# Sheet2.net
KiCad netlist of a schematic drawn in Altium Designer
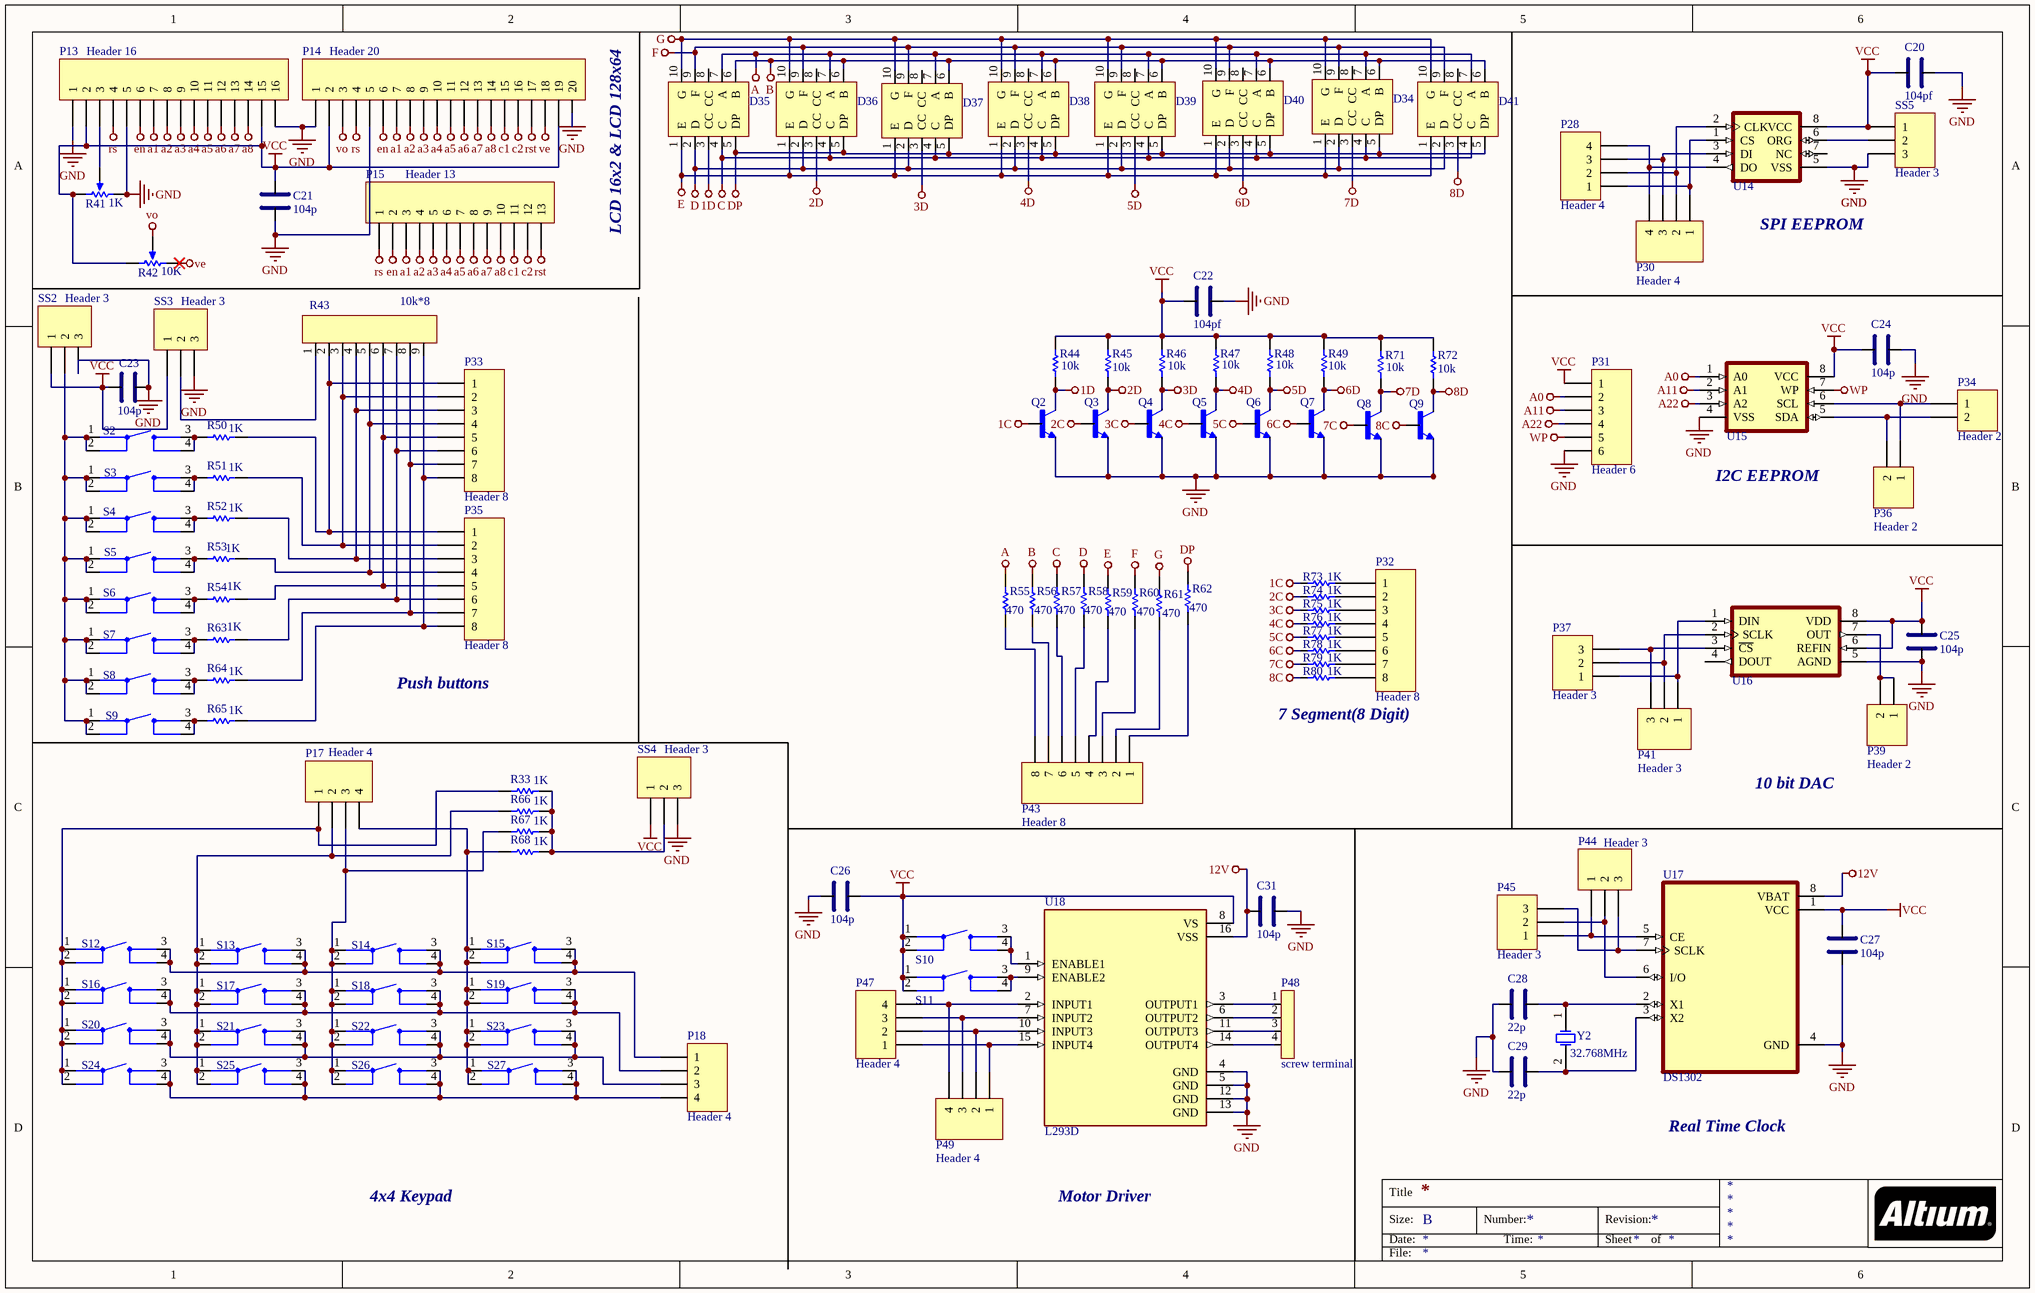
[diagram p0: Sheet2.SchDoc]

(export (version "E")
  (design (tool "Eeschema 10.0.6"))
  (components
    (comp (ref "C20")
      (value "104pf")
      (footprint "cap")
      (fields (field (name "Comment") "cap"))
      (libsource (lib "CAP") (part "cap"))
    )
    (comp (ref "C21")
      (value "104p")
      (footprint "cap")
      (fields (field (name "Comment") "cap"))
      (libsource (lib "CAP") (part "cap"))
    )
    (comp (ref "C22")
      (value "104pf")
      (footprint "cap")
      (fields (field (name "Comment") "cap"))
      (libsource (lib "CAP") (part "cap"))
    )
    (comp (ref "C23")
      (value "104p")
      (footprint "cap")
      (fields (field (name "Comment") "cap"))
      (libsource (lib "CAP") (part "cap"))
    )
    (comp (ref "C24")
      (value "104p")
      (footprint "cap")
      (fields (field (name "Comment") "cap"))
      (libsource (lib "CAP") (part "cap"))
    )
    (comp (ref "C25")
      (value "104p")
      (footprint "cap")
      (fields (field (name "Comment") "cap"))
      (libsource (lib "CAP") (part "cap"))
    )
    (comp (ref "C26")
      (value "104p")
      (footprint "cap")
      (fields (field (name "Comment") "cap"))
      (libsource (lib "CAP") (part "cap"))
    )
    (comp (ref "C27")
      (value "104p")
      (footprint "cap")
      (fields (field (name "Comment") "cap"))
      (libsource (lib "CAP") (part "cap"))
    )
    (comp (ref "C28")
      (value "22p")
      (footprint "cap")
      (fields (field (name "Comment") "cap"))
      (libsource (lib "CAP") (part "cap"))
    )
    (comp (ref "C29")
      (value "22p")
      (footprint "cap")
      (fields (field (name "Comment") "cap"))
      (libsource (lib "CAP") (part "cap"))
    )
    (comp (ref "C31")
      (value "104p")
      (footprint "cap")
      (fields (field (name "Comment") "cap"))
      (libsource (lib "CAP") (part "cap"))
    )
    (comp (ref "D34") (value "7seg") (footprint "LED_LTD-4708G") (libsource (lib "7seg") (part "7seg")))
    (comp (ref "D35") (value "7seg") (footprint "LED_LTD-4708G") (libsource (lib "7seg") (part "7seg")))
    (comp (ref "D36") (value "7seg") (footprint "LED_LTD-4708G") (libsource (lib "7seg") (part "7seg")))
    (comp (ref "D37") (value "7seg") (footprint "LED_LTD-4708G") (libsource (lib "7seg") (part "7seg")))
    (comp (ref "D38") (value "7seg") (footprint "LED_LTD-4708G") (libsource (lib "7seg") (part "7seg")))
    (comp (ref "D39") (value "7seg") (footprint "LED_LTD-4708G") (libsource (lib "7seg") (part "7seg")))
    (comp (ref "D40") (value "7seg") (footprint "LED_LTD-4708G") (libsource (lib "7seg") (part "7seg")))
    (comp (ref "D41") (value "7seg") (footprint "LED_LTD-4708G") (libsource (lib "7seg") (part "7seg")))
    (comp (ref "P13")
      (value "Header 16")
      (footprint "HDR1X16")
      (description "Header, 16-Pin")
      (fields (field (name "PUBLISHER") "Altium Limited"))
      (libsource (lib "Miscellaneous Connectors") (part "Header 16"))
    )
    (comp (ref "P14")
      (value "Header 20")
      (footprint "HDR1X20")
      (description "Header, 20-Pin")
      (fields (field (name "PUBLISHER") "Altium Limited"))
      (libsource (lib "Miscellaneous Connectors") (part "Header 20"))
    )
    (comp (ref "P15")
      (value "Header 13")
      (footprint "HDR1X13")
      (description "Header, 13-Pin")
      (fields (field (name "PUBLISHER") "Altium Limited"))
      (libsource (lib "Miscellaneous Connectors") (part "Header 13"))
    )
    (comp (ref "P17")
      (value "Header 4")
      (footprint "HDR1X4")
      (description "Header, 4-Pin")
      (fields (field (name "PUBLISHER") "Altium Limited"))
      (libsource (lib "") (part "Header 4_2"))
    )
    (comp (ref "P18")
      (value "Header 4")
      (footprint "HDR1X4")
      (description "Header, 4-Pin")
      (fields (field (name "PUBLISHER") "Altium Limited"))
      (libsource (lib "") (part "Header 4_3"))
    )
    (comp (ref "P28")
      (value "Header 4")
      (footprint "HDR1X4")
      (description "Header, 4-Pin")
      (fields (field (name "PUBLISHER") "Altium Limited"))
      (libsource (lib "Miscellaneous Connectors") (part "Header 4"))
    )
    (comp (ref "P30")
      (value "Header 4")
      (footprint "HDR1X4")
      (description "Header, 4-Pin")
      (fields (field (name "PUBLISHER") "Altium Limited"))
      (libsource (lib "") (part "Header 4_1"))
    )
    (comp (ref "P31")
      (value "Header 6")
      (footprint "HDR1X6")
      (description "Header, 6-Pin")
      (fields (field (name "PUBLISHER") "Altium Limited"))
      (libsource (lib "Miscellaneous Connectors") (part "Header 6"))
    )
    (comp (ref "P32")
      (value "Header 8")
      (footprint "HDR1X8")
      (description "Header, 8-Pin")
      (fields (field (name "PUBLISHER") "Altium Limited"))
      (libsource (lib "") (part "Header 8_1"))
    )
    (comp (ref "P33")
      (value "Header 8")
      (footprint "HDR1X8")
      (description "Header, 8-Pin")
      (fields (field (name "PUBLISHER") "Altium Limited"))
      (libsource (lib "") (part "Header 8_1"))
    )
    (comp (ref "P34")
      (value "Header 2")
      (footprint "HDR1X2")
      (description "Header, 2-Pin")
      (fields (field (name "PUBLISHER") "Altium Limited"))
      (libsource (lib "Miscellaneous Connectors") (part "Header 2"))
    )
    (comp (ref "P35")
      (value "Header 8")
      (footprint "HDR1X8")
      (description "Header, 8-Pin")
      (fields (field (name "PUBLISHER") "Altium Limited"))
      (libsource (lib "") (part "Header 8_1"))
    )
    (comp (ref "P36")
      (value "Header 2")
      (footprint "HDR1X2")
      (description "Header, 2-Pin")
      (fields (field (name "PUBLISHER") "Altium Limited"))
      (libsource (lib "") (part "Header 2_1"))
    )
    (comp (ref "P37")
      (value "Header 3")
      (footprint "HDR1X3")
      (description "Header, 3-Pin")
      (fields (field (name "PUBLISHER") "Altium Limited"))
      (libsource (lib "") (part "Header 3_3"))
    )
    (comp (ref "P39")
      (value "Header 2")
      (footprint "HDR1X2")
      (description "Header, 2-Pin")
      (fields (field (name "PUBLISHER") "Altium Limited"))
      (libsource (lib "") (part "Header 2_1"))
    )
    (comp (ref "P41")
      (value "Header 3")
      (footprint "HDR1X3")
      (description "Header, 3-Pin")
      (fields (field (name "PUBLISHER") "Altium Limited"))
      (libsource (lib "") (part "Header 3_1"))
    )
    (comp (ref "P43")
      (value "Header 8")
      (footprint "HDR1X8")
      (description "Header, 8-Pin")
      (fields (field (name "PUBLISHER") "Altium Limited"))
      (libsource (lib "Miscellaneous Connectors") (part "Header 8"))
    )
    (comp (ref "P44")
      (value "Header 3")
      (footprint "HDR1X3")
      (description "Header, 3-Pin")
      (fields (field (name "PUBLISHER") "Altium Limited"))
      (libsource (lib "Miscellaneous Connectors") (part "Header 3"))
    )
    (comp (ref "P45")
      (value "Header 3")
      (footprint "HDR1X3")
      (description "Header, 3-Pin")
      (fields (field (name "PUBLISHER") "Altium Limited"))
      (libsource (lib "") (part "Header 3_3"))
    )
    (comp (ref "P47")
      (value "Header 4")
      (footprint "HDR1X4")
      (description "Header, 4-Pin")
      (fields (field (name "PUBLISHER") "Altium Limited"))
      (libsource (lib "Miscellaneous Connectors") (part "Header 4"))
    )
    (comp (ref "P48")
      (value "screw terminal")
      (footprint "screw library")
      (libsource (lib "screw terminal") (part "screw terminal"))
    )
    (comp (ref "P49")
      (value "Header 4")
      (footprint "HDR1X4")
      (description "Header, 4-Pin")
      (fields (field (name "PUBLISHER") "Altium Limited"))
      (libsource (lib "") (part "Header 4_1"))
    )
    (comp (ref "Q2")
      (value "2N5172")
      (footprint "TRANSISTOR_TO-92:TRANSISTOR_TO-92")
      (description "Bipolar (BJT) Transistor NPN 25V 500mA 625mW Through Hole TO-92-3")
      (fields (field (name "MF") "ON Semiconductor"))
      (libsource (lib "2N5172") (part "2N5172"))
    )
    (comp (ref "Q3")
      (value "2N5172")
      (footprint "TRANSISTOR_TO-92:TRANSISTOR_TO-92")
      (description "Bipolar (BJT) Transistor NPN 25V 500mA 625mW Through Hole TO-92-3")
      (fields (field (name "MF") "ON Semiconductor"))
      (libsource (lib "2N5172") (part "2N5172"))
    )
    (comp (ref "Q4")
      (value "2N5172")
      (footprint "TRANSISTOR_TO-92:TRANSISTOR_TO-92")
      (description "Bipolar (BJT) Transistor NPN 25V 500mA 625mW Through Hole TO-92-3")
      (fields (field (name "MF") "ON Semiconductor"))
      (libsource (lib "2N5172") (part "2N5172"))
    )
    (comp (ref "Q5")
      (value "2N5172")
      (footprint "TRANSISTOR_TO-92:TRANSISTOR_TO-92")
      (description "Bipolar (BJT) Transistor NPN 25V 500mA 625mW Through Hole TO-92-3")
      (fields (field (name "MF") "ON Semiconductor"))
      (libsource (lib "2N5172") (part "2N5172"))
    )
    (comp (ref "Q6")
      (value "2N5172")
      (footprint "TRANSISTOR_TO-92:TRANSISTOR_TO-92")
      (description "Bipolar (BJT) Transistor NPN 25V 500mA 625mW Through Hole TO-92-3")
      (fields (field (name "MF") "ON Semiconductor"))
      (libsource (lib "2N5172") (part "2N5172"))
    )
    (comp (ref "Q7")
      (value "2N5172")
      (footprint "TRANSISTOR_TO-92:TRANSISTOR_TO-92")
      (description "Bipolar (BJT) Transistor NPN 25V 500mA 625mW Through Hole TO-92-3")
      (fields (field (name "MF") "ON Semiconductor"))
      (libsource (lib "2N5172") (part "2N5172"))
    )
    (comp (ref "Q8")
      (value "2N5172")
      (footprint "TRANSISTOR_TO-92:TRANSISTOR_TO-92")
      (description "Bipolar (BJT) Transistor NPN 25V 500mA 625mW Through Hole TO-92-3")
      (fields (field (name "MF") "ON Semiconductor"))
      (libsource (lib "2N5172") (part "2N5172"))
    )
    (comp (ref "Q9")
      (value "2N5172")
      (footprint "TRANSISTOR_TO-92:TRANSISTOR_TO-92")
      (description "Bipolar (BJT) Transistor NPN 25V 500mA 625mW Through Hole TO-92-3")
      (fields (field (name "MF") "ON Semiconductor"))
      (libsource (lib "2N5172") (part "2N5172"))
    )
    (comp (ref "R33")
      (value "1K")
      (footprint "AXIAL-0.3")
      (description "Resistor")
      (fields (field (name "Comment") "Res1") (field (name "PUBLISHER") "Altium Limited"))
      (libsource (lib "Miscellaneous Devices") (part "Res1"))
    )
    (comp (ref "R41")
      (value "1K")
      (footprint "VR5")
      (description "Potentiometer")
      (fields (field (name "Comment") "RPot") (field (name "PUBLISHER") "Altium Limited"))
      (libsource (lib "Miscellaneous Devices") (part "RPot"))
    )
    (comp (ref "R42")
      (value "10K")
      (footprint "VR5")
      (description "Potentiometer")
      (fields (field (name "Comment") "RPot") (field (name "PUBLISHER") "Altium Limited"))
      (libsource (lib "Miscellaneous Devices") (part "RPot"))
    )
    (comp (ref "R43")
      (value "10k*8")
      (footprint "10k sip")
      (fields (field (name "Comment") "10k sip"))
      (libsource (lib "10k sip") (part "10k sip"))
    )
    (comp (ref "R44")
      (value "10k")
      (footprint "AXIAL-0.3")
      (description "Resistor")
      (fields (field (name "Comment") "Res1") (field (name "PUBLISHER") "Altium Limited"))
      (libsource (lib "Miscellaneous Devices") (part "Res1"))
    )
    (comp (ref "R45")
      (value "10k")
      (footprint "AXIAL-0.3")
      (description "Resistor")
      (fields (field (name "Comment") "Res1") (field (name "PUBLISHER") "Altium Limited"))
      (libsource (lib "Miscellaneous Devices") (part "Res1"))
    )
    (comp (ref "R46")
      (value "10k")
      (footprint "AXIAL-0.3")
      (description "Resistor")
      (fields (field (name "Comment") "Res1") (field (name "PUBLISHER") "Altium Limited"))
      (libsource (lib "Miscellaneous Devices") (part "Res1"))
    )
    (comp (ref "R47")
      (value "10k")
      (footprint "AXIAL-0.3")
      (description "Resistor")
      (fields (field (name "Comment") "Res1") (field (name "PUBLISHER") "Altium Limited"))
      (libsource (lib "Miscellaneous Devices") (part "Res1"))
    )
    (comp (ref "R48")
      (value "10k")
      (footprint "AXIAL-0.3")
      (description "Resistor")
      (fields (field (name "Comment") "Res1") (field (name "PUBLISHER") "Altium Limited"))
      (libsource (lib "Miscellaneous Devices") (part "Res1"))
    )
    (comp (ref "R49")
      (value "10k")
      (footprint "AXIAL-0.3")
      (description "Resistor")
      (fields (field (name "Comment") "Res1") (field (name "PUBLISHER") "Altium Limited"))
      (libsource (lib "Miscellaneous Devices") (part "Res1"))
    )
    (comp (ref "R50")
      (value "1K")
      (footprint "AXIAL-0.3")
      (description "Resistor")
      (fields (field (name "Comment") "Res1") (field (name "PUBLISHER") "Altium Limited"))
      (libsource (lib "Miscellaneous Devices") (part "Res1"))
    )
    (comp (ref "R51")
      (value "1K")
      (footprint "AXIAL-0.3")
      (description "Resistor")
      (fields (field (name "Comment") "Res1") (field (name "PUBLISHER") "Altium Limited"))
      (libsource (lib "Miscellaneous Devices") (part "Res1"))
    )
    (comp (ref "R52")
      (value "1K")
      (footprint "AXIAL-0.3")
      (description "Resistor")
      (fields (field (name "Comment") "Res1") (field (name "PUBLISHER") "Altium Limited"))
      (libsource (lib "Miscellaneous Devices") (part "Res1"))
    )
    (comp (ref "R53")
      (value "1K")
      (footprint "AXIAL-0.3")
      (description "Resistor")
      (fields (field (name "Comment") "Res1") (field (name "PUBLISHER") "Altium Limited"))
      (libsource (lib "Miscellaneous Devices") (part "Res1"))
    )
    (comp (ref "R54")
      (value "1K")
      (footprint "AXIAL-0.3")
      (description "Resistor")
      (fields (field (name "Comment") "Res1") (field (name "PUBLISHER") "Altium Limited"))
      (libsource (lib "Miscellaneous Devices") (part "Res1"))
    )
    (comp (ref "R55")
      (value "470")
      (footprint "AXIAL-0.3")
      (description "Resistor")
      (fields (field (name "Comment") "Res1") (field (name "PUBLISHER") "Altium Limited"))
      (libsource (lib "Miscellaneous Devices") (part "Res1"))
    )
    (comp (ref "R56")
      (value "470")
      (footprint "AXIAL-0.3")
      (description "Resistor")
      (fields (field (name "Comment") "Res1") (field (name "PUBLISHER") "Altium Limited"))
      (libsource (lib "Miscellaneous Devices") (part "Res1"))
    )
    (comp (ref "R57")
      (value "470")
      (footprint "AXIAL-0.3")
      (description "Resistor")
      (fields (field (name "Comment") "Res1") (field (name "PUBLISHER") "Altium Limited"))
      (libsource (lib "Miscellaneous Devices") (part "Res1"))
    )
    (comp (ref "R58")
      (value "470")
      (footprint "AXIAL-0.3")
      (description "Resistor")
      (fields (field (name "Comment") "Res1") (field (name "PUBLISHER") "Altium Limited"))
      (libsource (lib "Miscellaneous Devices") (part "Res1"))
    )
    (comp (ref "R59")
      (value "470")
      (footprint "AXIAL-0.3")
      (description "Resistor")
      (fields (field (name "Comment") "Res1") (field (name "PUBLISHER") "Altium Limited"))
      (libsource (lib "Miscellaneous Devices") (part "Res1"))
    )
    (comp (ref "R60")
      (value "470")
      (footprint "AXIAL-0.3")
      (description "Resistor")
      (fields (field (name "Comment") "Res1") (field (name "PUBLISHER") "Altium Limited"))
      (libsource (lib "Miscellaneous Devices") (part "Res1"))
    )
    (comp (ref "R61")
      (value "470")
      (footprint "AXIAL-0.3")
      (description "Resistor")
      (fields (field (name "Comment") "Res1") (field (name "PUBLISHER") "Altium Limited"))
      (libsource (lib "Miscellaneous Devices") (part "Res1"))
    )
    (comp (ref "R62")
      (value "470")
      (footprint "AXIAL-0.3")
      (description "Resistor")
      (fields (field (name "Comment") "Res1") (field (name "PUBLISHER") "Altium Limited"))
      (libsource (lib "Miscellaneous Devices") (part "Res1"))
    )
    (comp (ref "R63")
      (value "1K")
      (footprint "AXIAL-0.3")
      (description "Resistor")
      (fields (field (name "Comment") "Res1") (field (name "PUBLISHER") "Altium Limited"))
      (libsource (lib "Miscellaneous Devices") (part "Res1"))
    )
    (comp (ref "R64")
      (value "1K")
      (footprint "AXIAL-0.3")
      (description "Resistor")
      (fields (field (name "Comment") "Res1") (field (name "PUBLISHER") "Altium Limited"))
      (libsource (lib "Miscellaneous Devices") (part "Res1"))
    )
    (comp (ref "R65")
      (value "1K")
      (footprint "AXIAL-0.3")
      (description "Resistor")
      (fields (field (name "Comment") "Res1") (field (name "PUBLISHER") "Altium Limited"))
      (libsource (lib "Miscellaneous Devices") (part "Res1"))
    )
    (comp (ref "R66")
      (value "1K")
      (footprint "AXIAL-0.3")
      (description "Resistor")
      (fields (field (name "Comment") "Res1") (field (name "PUBLISHER") "Altium Limited"))
      (libsource (lib "Miscellaneous Devices") (part "Res1"))
    )
    (comp (ref "R67")
      (value "1K")
      (footprint "AXIAL-0.3")
      (description "Resistor")
      (fields (field (name "Comment") "Res1") (field (name "PUBLISHER") "Altium Limited"))
      (libsource (lib "Miscellaneous Devices") (part "Res1"))
    )
    (comp (ref "R68")
      (value "1K")
      (footprint "AXIAL-0.3")
      (description "Resistor")
      (fields (field (name "Comment") "Res1") (field (name "PUBLISHER") "Altium Limited"))
      (libsource (lib "Miscellaneous Devices") (part "Res1"))
    )
    (comp (ref "R71")
      (value "10k")
      (footprint "AXIAL-0.3")
      (description "Resistor")
      (fields (field (name "Comment") "Res1") (field (name "PUBLISHER") "Altium Limited"))
      (libsource (lib "Miscellaneous Devices") (part "Res1"))
    )
    (comp (ref "R72")
      (value "10k")
      (footprint "AXIAL-0.3")
      (description "Resistor")
      (fields (field (name "Comment") "Res1") (field (name "PUBLISHER") "Altium Limited"))
      (libsource (lib "Miscellaneous Devices") (part "Res1"))
    )
    (comp (ref "R73")
      (value "1K")
      (footprint "AXIAL-0.3")
      (description "Resistor")
      (fields (field (name "Comment") "Res1") (field (name "PUBLISHER") "Altium Limited"))
      (libsource (lib "Miscellaneous Devices") (part "Res1"))
    )
    (comp (ref "R74")
      (value "1K")
      (footprint "AXIAL-0.3")
      (description "Resistor")
      (fields (field (name "Comment") "Res1") (field (name "PUBLISHER") "Altium Limited"))
      (libsource (lib "Miscellaneous Devices") (part "Res1"))
    )
    (comp (ref "R75")
      (value "1K")
      (footprint "AXIAL-0.3")
      (description "Resistor")
      (fields (field (name "Comment") "Res1") (field (name "PUBLISHER") "Altium Limited"))
      (libsource (lib "Miscellaneous Devices") (part "Res1"))
    )
    (comp (ref "R76")
      (value "1K")
      (footprint "AXIAL-0.3")
      (description "Resistor")
      (fields (field (name "Comment") "Res1") (field (name "PUBLISHER") "Altium Limited"))
      (libsource (lib "Miscellaneous Devices") (part "Res1"))
    )
    (comp (ref "R77")
      (value "1K")
      (footprint "AXIAL-0.3")
      (description "Resistor")
      (fields (field (name "Comment") "Res1") (field (name "PUBLISHER") "Altium Limited"))
      (libsource (lib "Miscellaneous Devices") (part "Res1"))
    )
    (comp (ref "R78")
      (value "1K")
      (footprint "AXIAL-0.3")
      (description "Resistor")
      (fields (field (name "Comment") "Res1") (field (name "PUBLISHER") "Altium Limited"))
      (libsource (lib "Miscellaneous Devices") (part "Res1"))
    )
    (comp (ref "R79")
      (value "1K")
      (footprint "AXIAL-0.3")
      (description "Resistor")
      (fields (field (name "Comment") "Res1") (field (name "PUBLISHER") "Altium Limited"))
      (libsource (lib "Miscellaneous Devices") (part "Res1"))
    )
    (comp (ref "R80")
      (value "1K")
      (footprint "AXIAL-0.3")
      (description "Resistor")
      (fields (field (name "Comment") "Res1") (field (name "PUBLISHER") "Altium Limited"))
      (libsource (lib "Miscellaneous Devices") (part "Res1"))
    )
    (comp (ref "S2")
      (value "SKHHANA010")
      (footprint "buttons:buttons")
      (description "Switch Tactile N.O. SPST Round Button PC Pins 0.05A 12VDC 0.98N Thru-Hole Bulk")
      (fields (field (name "MF") "ALPS"))
      (libsource (lib "SnapEDAsch") (part "SKHHANA010"))
    )
    (comp (ref "S3")
      (value "SKHHANA010")
      (footprint "buttons:buttons")
      (description "Switch Tactile N.O. SPST Round Button PC Pins 0.05A 12VDC 0.98N Thru-Hole Bulk")
      (fields (field (name "MF") "ALPS"))
      (libsource (lib "SnapEDAsch") (part "SKHHANA010"))
    )
    (comp (ref "S4")
      (value "SKHHANA010")
      (footprint "buttons:buttons")
      (description "Switch Tactile N.O. SPST Round Button PC Pins 0.05A 12VDC 0.98N Thru-Hole Bulk")
      (fields (field (name "MF") "ALPS"))
      (libsource (lib "SnapEDAsch") (part "SKHHANA010"))
    )
    (comp (ref "S5")
      (value "SKHHANA010")
      (footprint "buttons:buttons")
      (description "Switch Tactile N.O. SPST Round Button PC Pins 0.05A 12VDC 0.98N Thru-Hole Bulk")
      (fields (field (name "MF") "ALPS"))
      (libsource (lib "SnapEDAsch") (part "SKHHANA010"))
    )
    (comp (ref "S6")
      (value "SKHHANA010")
      (footprint "buttons:buttons")
      (description "Switch Tactile N.O. SPST Round Button PC Pins 0.05A 12VDC 0.98N Thru-Hole Bulk")
      (fields (field (name "MF") "ALPS"))
      (libsource (lib "SnapEDAsch") (part "SKHHANA010"))
    )
    (comp (ref "S7")
      (value "SKHHANA010")
      (footprint "buttons:buttons")
      (description "Switch Tactile N.O. SPST Round Button PC Pins 0.05A 12VDC 0.98N Thru-Hole Bulk")
      (fields (field (name "MF") "ALPS"))
      (libsource (lib "SnapEDAsch") (part "SKHHANA010"))
    )
    (comp (ref "S8")
      (value "SKHHANA010")
      (footprint "buttons:buttons")
      (description "Switch Tactile N.O. SPST Round Button PC Pins 0.05A 12VDC 0.98N Thru-Hole Bulk")
      (fields (field (name "MF") "ALPS"))
      (libsource (lib "SnapEDAsch") (part "SKHHANA010"))
    )
    (comp (ref "S9")
      (value "SKHHANA010")
      (footprint "buttons:buttons")
      (description "Switch Tactile N.O. SPST Round Button PC Pins 0.05A 12VDC 0.98N Thru-Hole Bulk")
      (fields (field (name "MF") "ALPS"))
      (libsource (lib "SnapEDAsch") (part "SKHHANA010"))
    )
    (comp (ref "S10")
      (value "SKHHANA010")
      (footprint "buttons:buttons")
      (description "Switch Tactile N.O. SPST Round Button PC Pins 0.05A 12VDC 0.98N Thru-Hole Bulk")
      (fields (field (name "MF") "ALPS"))
      (libsource (lib "SnapEDAsch") (part "SKHHANA010"))
    )
    (comp (ref "S11")
      (value "SKHHANA010")
      (footprint "buttons:buttons")
      (description "Switch Tactile N.O. SPST Round Button PC Pins 0.05A 12VDC 0.98N Thru-Hole Bulk")
      (fields (field (name "MF") "ALPS"))
      (libsource (lib "SnapEDAsch") (part "SKHHANA010"))
    )
    (comp (ref "S12")
      (value "SKHHANA010")
      (footprint "buttons:buttons")
      (description "Switch Tactile N.O. SPST Round Button PC Pins 0.05A 12VDC 0.98N Thru-Hole Bulk")
      (fields (field (name "MF") "ALPS"))
      (libsource (lib "SnapEDAsch") (part "SKHHANA010"))
    )
    (comp (ref "S13")
      (value "SKHHANA010")
      (footprint "buttons:buttons")
      (description "Switch Tactile N.O. SPST Round Button PC Pins 0.05A 12VDC 0.98N Thru-Hole Bulk")
      (fields (field (name "MF") "ALPS"))
      (libsource (lib "SnapEDAsch") (part "SKHHANA010"))
    )
    (comp (ref "S14")
      (value "SKHHANA010")
      (footprint "buttons:buttons")
      (description "Switch Tactile N.O. SPST Round Button PC Pins 0.05A 12VDC 0.98N Thru-Hole Bulk")
      (fields (field (name "MF") "ALPS"))
      (libsource (lib "SnapEDAsch") (part "SKHHANA010"))
    )
    (comp (ref "S15")
      (value "SKHHANA010")
      (footprint "buttons:buttons")
      (description "Switch Tactile N.O. SPST Round Button PC Pins 0.05A 12VDC 0.98N Thru-Hole Bulk")
      (fields (field (name "MF") "ALPS"))
      (libsource (lib "SnapEDAsch") (part "SKHHANA010"))
    )
    (comp (ref "S16")
      (value "SKHHANA010")
      (footprint "buttons:buttons")
      (description "Switch Tactile N.O. SPST Round Button PC Pins 0.05A 12VDC 0.98N Thru-Hole Bulk")
      (fields (field (name "MF") "ALPS"))
      (libsource (lib "SnapEDAsch") (part "SKHHANA010"))
    )
    (comp (ref "S17")
      (value "SKHHANA010")
      (footprint "buttons:buttons")
      (description "Switch Tactile N.O. SPST Round Button PC Pins 0.05A 12VDC 0.98N Thru-Hole Bulk")
      (fields (field (name "MF") "ALPS"))
      (libsource (lib "SnapEDAsch") (part "SKHHANA010"))
    )
    (comp (ref "S18")
      (value "SKHHANA010")
      (footprint "buttons:buttons")
      (description "Switch Tactile N.O. SPST Round Button PC Pins 0.05A 12VDC 0.98N Thru-Hole Bulk")
      (fields (field (name "MF") "ALPS"))
      (libsource (lib "SnapEDAsch") (part "SKHHANA010"))
    )
    (comp (ref "S19")
      (value "SKHHANA010")
      (footprint "buttons:buttons")
      (description "Switch Tactile N.O. SPST Round Button PC Pins 0.05A 12VDC 0.98N Thru-Hole Bulk")
      (fields (field (name "MF") "ALPS"))
      (libsource (lib "SnapEDAsch") (part "SKHHANA010"))
    )
    (comp (ref "S20")
      (value "SKHHANA010")
      (footprint "buttons:buttons")
      (description "Switch Tactile N.O. SPST Round Button PC Pins 0.05A 12VDC 0.98N Thru-Hole Bulk")
      (fields (field (name "MF") "ALPS"))
      (libsource (lib "SnapEDAsch") (part "SKHHANA010"))
    )
    (comp (ref "S21")
      (value "SKHHANA010")
      (footprint "buttons:buttons")
      (description "Switch Tactile N.O. SPST Round Button PC Pins 0.05A 12VDC 0.98N Thru-Hole Bulk")
      (fields (field (name "MF") "ALPS"))
      (libsource (lib "SnapEDAsch") (part "SKHHANA010"))
    )
    (comp (ref "S22")
      (value "SKHHANA010")
      (footprint "buttons:buttons")
      (description "Switch Tactile N.O. SPST Round Button PC Pins 0.05A 12VDC 0.98N Thru-Hole Bulk")
      (fields (field (name "MF") "ALPS"))
      (libsource (lib "SnapEDAsch") (part "SKHHANA010"))
    )
    (comp (ref "S23")
      (value "SKHHANA010")
      (footprint "buttons:buttons")
      (description "Switch Tactile N.O. SPST Round Button PC Pins 0.05A 12VDC 0.98N Thru-Hole Bulk")
      (fields (field (name "MF") "ALPS"))
      (libsource (lib "SnapEDAsch") (part "SKHHANA010"))
    )
    (comp (ref "S24")
      (value "SKHHANA010")
      (footprint "buttons:buttons")
      (description "Switch Tactile N.O. SPST Round Button PC Pins 0.05A 12VDC 0.98N Thru-Hole Bulk")
      (fields (field (name "MF") "ALPS"))
      (libsource (lib "SnapEDAsch") (part "SKHHANA010"))
    )
    (comp (ref "S25")
      (value "SKHHANA010")
      (footprint "buttons:buttons")
      (description "Switch Tactile N.O. SPST Round Button PC Pins 0.05A 12VDC 0.98N Thru-Hole Bulk")
      (fields (field (name "MF") "ALPS"))
      (libsource (lib "SnapEDAsch") (part "SKHHANA010"))
    )
    (comp (ref "S26")
      (value "SKHHANA010")
      (footprint "buttons:buttons")
      (description "Switch Tactile N.O. SPST Round Button PC Pins 0.05A 12VDC 0.98N Thru-Hole Bulk")
      (fields (field (name "MF") "ALPS"))
      (libsource (lib "SnapEDAsch") (part "SKHHANA010"))
    )
    (comp (ref "S27")
      (value "SKHHANA010")
      (footprint "buttons:buttons")
      (description "Switch Tactile N.O. SPST Round Button PC Pins 0.05A 12VDC 0.98N Thru-Hole Bulk")
      (fields (field (name "MF") "ALPS"))
      (libsource (lib "SnapEDAsch") (part "SKHHANA010"))
    )
    (comp (ref "SS2")
      (value "Header 3")
      (footprint "HDR1X3")
      (description "Header, 3-Pin")
      (fields (field (name "PUBLISHER") "Altium Limited"))
      (libsource (lib "Miscellaneous Connectors") (part "Header 3"))
    )
    (comp (ref "SS3")
      (value "Header 3")
      (footprint "HDR1X3")
      (description "Header, 3-Pin")
      (fields (field (name "PUBLISHER") "Altium Limited"))
      (libsource (lib "Miscellaneous Connectors") (part "Header 3"))
    )
    (comp (ref "SS4")
      (value "Header 3")
      (footprint "HDR1X3")
      (description "Header, 3-Pin")
      (fields (field (name "PUBLISHER") "Altium Limited"))
      (libsource (lib "Miscellaneous Connectors") (part "Header 3"))
    )
    (comp (ref "SS5")
      (value "Header 3")
      (footprint "HDR1X3")
      (description "Header, 3-Pin")
      (fields (field (name "PUBLISHER") "Altium Limited"))
      (libsource (lib "") (part "Header 3_2"))
    )
    (comp (ref "U14")
      (value "93LC46A/P")
      (footprint "PIC(8)pinbasic:PIC10F220")
      (description "EEPROM Memory IC 1Kb (128 x 8) SPI 2MHz 8-PDIP")
      (fields (field (name "MF") "Microchip"))
      (libsource (lib "93LC46A_P") (part "93LC46A/P"))
    )
    (comp (ref "U15")
      (value "24AA1025")
      (footprint "PIC(8)pinbasic:PIC10F220")
      (description "EEPROM Memory IC 1Mb (128K x 8) IÂ²C 400kHz 900ns 8-PDIP")
      (fields (field (name "MP") "24AA1025-I/P") (field (name "MF") "Microchip"))
      (libsource (lib "24AA1025-I_P") (part "24AA1025-I/P"))
    )
    (comp (ref "U16")
      (value "TLC5615")
      (footprint "PIC(8)pinbasic:PIC10F220")
      (description "10-bit, single-channel, low-power DAC with 12.5us settling time and power-on reset 8-PDIP 0 to 70")
      (fields (field (name "MP") "TLC5615CP") (field (name "MF") "Texas Instruments"))
      (libsource (lib "TLC5615CP") (part "TLC5615CP"))
    )
    (comp (ref "U17")
      (value "DS1302")
      (footprint "PIC(8)pinbasic:PIC10F220")
      (description "Real Time Clock _RTC_ IC Clock/Calendar 31B 8-DIP _0.300, 7.62mm_")
      (fields (field (name "DIGI-KEY_PART_NUMBER") "DS1302+-ND") (field (name "MP") "DS1302+"))
      (libsource (lib "SnapEDAsch") (part "DS1302"))
    )
    (comp (ref "U18") (value "L293D") (footprint "L293D") (libsource (lib "L293D") (part "L293D")))
    (comp (ref "Y2")
      (value "32.768MHz")
      (footprint "R38")
      (description "Crystal Oscillator")
      (fields (field (name "Comment") "XTAL") (field (name "PUBLISHER") "Altium Limited"))
      (libsource (lib "Miscellaneous Devices") (part "XTAL"))
    )
  )
  (nets
    (net (code "1") (name "1C") (class "Default")
      (node (ref "Q2") (pin "2") (pinfunction "B_2") (pintype "passive"))
      (node (ref "R73") (pin "1") (pinfunction "1_1") (pintype "passive"))
    )
    (net (code "2") (name "1D") (class "Default")
      (node (ref "D35") (pin "3") (pinfunction "CC_3") (pintype "passive"))
      (node (ref "Q2") (pin "1") (pinfunction "C_1") (pintype "passive"))
      (node (ref "R44") (pin "1") (pinfunction "1_1") (pintype "passive"))
    )
    (net (code "3") (name "2C") (class "Default")
      (node (ref "Q3") (pin "2") (pinfunction "B_2") (pintype "passive"))
      (node (ref "R74") (pin "1") (pinfunction "1_1") (pintype "passive"))
    )
    (net (code "4") (name "2D") (class "Default")
      (node (ref "D36") (pin "3") (pinfunction "CC_3") (pintype "passive"))
      (node (ref "Q3") (pin "1") (pinfunction "C_1") (pintype "passive"))
      (node (ref "R45") (pin "1") (pinfunction "1_1") (pintype "passive"))
    )
    (net (code "5") (name "3C") (class "Default")
      (node (ref "Q4") (pin "2") (pinfunction "B_2") (pintype "passive"))
      (node (ref "R75") (pin "1") (pinfunction "1_1") (pintype "passive"))
    )
    (net (code "6") (name "3D") (class "Default")
      (node (ref "D37") (pin "3") (pinfunction "CC_3") (pintype "passive"))
      (node (ref "Q4") (pin "1") (pinfunction "C_1") (pintype "passive"))
      (node (ref "R46") (pin "1") (pinfunction "1_1") (pintype "passive"))
    )
    (net (code "7") (name "4C") (class "Default")
      (node (ref "Q5") (pin "2") (pinfunction "B_2") (pintype "passive"))
      (node (ref "R76") (pin "1") (pinfunction "1_1") (pintype "passive"))
    )
    (net (code "8") (name "4D") (class "Default")
      (node (ref "D38") (pin "3") (pinfunction "CC_3") (pintype "passive"))
      (node (ref "Q5") (pin "1") (pinfunction "C_1") (pintype "passive"))
      (node (ref "R47") (pin "1") (pinfunction "1_1") (pintype "passive"))
    )
    (net (code "9") (name "5C") (class "Default")
      (node (ref "Q6") (pin "2") (pinfunction "B_2") (pintype "passive"))
      (node (ref "R77") (pin "1") (pinfunction "1_1") (pintype "passive"))
    )
    (net (code "10") (name "5D") (class "Default")
      (node (ref "D39") (pin "3") (pinfunction "CC_3") (pintype "passive"))
      (node (ref "Q6") (pin "1") (pinfunction "C_1") (pintype "passive"))
      (node (ref "R48") (pin "1") (pinfunction "1_1") (pintype "passive"))
    )
    (net (code "11") (name "6C") (class "Default")
      (node (ref "Q7") (pin "2") (pinfunction "B_2") (pintype "passive"))
      (node (ref "R78") (pin "1") (pinfunction "1_1") (pintype "passive"))
    )
    (net (code "12") (name "6D") (class "Default")
      (node (ref "D40") (pin "3") (pinfunction "CC_3") (pintype "passive"))
      (node (ref "Q7") (pin "1") (pinfunction "C_1") (pintype "passive"))
      (node (ref "R49") (pin "1") (pinfunction "1_1") (pintype "passive"))
    )
    (net (code "13") (name "7C") (class "Default")
      (node (ref "Q8") (pin "2") (pinfunction "B_2") (pintype "passive"))
      (node (ref "R79") (pin "1") (pinfunction "1_1") (pintype "passive"))
    )
    (net (code "14") (name "7D") (class "Default")
      (node (ref "D34") (pin "3") (pinfunction "CC_3") (pintype "passive"))
      (node (ref "Q8") (pin "1") (pinfunction "C_1") (pintype "passive"))
      (node (ref "R71") (pin "1") (pinfunction "1_1") (pintype "passive"))
    )
    (net (code "15") (name "8C") (class "Default")
      (node (ref "Q9") (pin "2") (pinfunction "B_2") (pintype "passive"))
      (node (ref "R80") (pin "1") (pinfunction "1_1") (pintype "passive"))
    )
    (net (code "16") (name "8D") (class "Default")
      (node (ref "D41") (pin "3") (pinfunction "CC_3") (pintype "passive"))
      (node (ref "Q9") (pin "1") (pinfunction "C_1") (pintype "passive"))
      (node (ref "R72") (pin "1") (pinfunction "1_1") (pintype "passive"))
    )
    (net (code "17") (name "12V") (class "Default")
      (node (ref "C31") (pin "2") (pinfunction "2_2") (pintype "passive"))
      (node (ref "U17") (pin "8") (pinfunction "VBAT_8") (pintype "power_in"))
      (node (ref "U18") (pin "16") (pinfunction "VSS_16") (pintype "power_in"))
    )
    (net (code "18") (name "A") (class "Default")
      (node (ref "D34") (pin "7") (pinfunction "A_7") (pintype "passive"))
      (node (ref "D35") (pin "7") (pinfunction "A_7") (pintype "passive"))
      (node (ref "D36") (pin "7") (pinfunction "A_7") (pintype "passive"))
      (node (ref "D37") (pin "7") (pinfunction "A_7") (pintype "passive"))
      (node (ref "D38") (pin "7") (pinfunction "A_7") (pintype "passive"))
      (node (ref "D39") (pin "7") (pinfunction "A_7") (pintype "passive"))
      (node (ref "D40") (pin "7") (pinfunction "A_7") (pintype "passive"))
      (node (ref "D41") (pin "7") (pinfunction "A_7") (pintype "passive"))
      (node (ref "R55") (pin "2") (pinfunction "2_2") (pintype "passive"))
    )
    (net (code "19") (name "A0") (class "Default")
      (node (ref "P31") (pin "2") (pinfunction "2_2") (pintype "passive"))
      (node (ref "U15") (pin "1") (pinfunction "A0_1") (pintype "input"))
    )
    (net (code "20") (name "A11") (class "Default")
      (node (ref "P31") (pin "3") (pinfunction "3_3") (pintype "passive"))
      (node (ref "U15") (pin "2") (pinfunction "A1_2") (pintype "input"))
    )
    (net (code "21") (name "A22") (class "Default")
      (node (ref "P31") (pin "4") (pinfunction "4_4") (pintype "passive"))
      (node (ref "U15") (pin "3") (pinfunction "A2_3") (pintype "input"))
    )
    (net (code "22") (name "B") (class "Default")
      (node (ref "D34") (pin "6") (pinfunction "B_6") (pintype "passive"))
      (node (ref "D35") (pin "6") (pinfunction "B_6") (pintype "passive"))
      (node (ref "D36") (pin "6") (pinfunction "B_6") (pintype "passive"))
      (node (ref "D37") (pin "6") (pinfunction "B_6") (pintype "passive"))
      (node (ref "D38") (pin "6") (pinfunction "B_6") (pintype "passive"))
      (node (ref "D39") (pin "6") (pinfunction "B_6") (pintype "passive"))
      (node (ref "D40") (pin "6") (pinfunction "B_6") (pintype "passive"))
      (node (ref "D41") (pin "6") (pinfunction "B_6") (pintype "passive"))
      (node (ref "R56") (pin "2") (pinfunction "2_2") (pintype "passive"))
    )
    (net (code "23") (name "C") (class "Default")
      (node (ref "D34") (pin "4") (pinfunction "C_4") (pintype "passive"))
      (node (ref "D35") (pin "4") (pinfunction "C_4") (pintype "passive"))
      (node (ref "D36") (pin "4") (pinfunction "C_4") (pintype "passive"))
      (node (ref "D37") (pin "4") (pinfunction "C_4") (pintype "passive"))
      (node (ref "D38") (pin "4") (pinfunction "C_4") (pintype "passive"))
      (node (ref "D39") (pin "4") (pinfunction "C_4") (pintype "passive"))
      (node (ref "D40") (pin "4") (pinfunction "C_4") (pintype "passive"))
      (node (ref "D41") (pin "4") (pinfunction "C_4") (pintype "passive"))
      (node (ref "R57") (pin "2") (pinfunction "2_2") (pintype "passive"))
    )
    (net (code "24") (name "D") (class "Default")
      (node (ref "D34") (pin "2") (pinfunction "D_2") (pintype "passive"))
      (node (ref "D35") (pin "2") (pinfunction "D_2") (pintype "passive"))
      (node (ref "D36") (pin "2") (pinfunction "D_2") (pintype "passive"))
      (node (ref "D37") (pin "2") (pinfunction "D_2") (pintype "passive"))
      (node (ref "D38") (pin "2") (pinfunction "D_2") (pintype "passive"))
      (node (ref "D39") (pin "2") (pinfunction "D_2") (pintype "passive"))
      (node (ref "D40") (pin "2") (pinfunction "D_2") (pintype "passive"))
      (node (ref "D41") (pin "2") (pinfunction "D_2") (pintype "passive"))
      (node (ref "R58") (pin "2") (pinfunction "2_2") (pintype "passive"))
    )
    (net (code "25") (name "DP") (class "Default")
      (node (ref "D34") (pin "5") (pinfunction "DP_5") (pintype "passive"))
      (node (ref "D35") (pin "5") (pinfunction "DP_5") (pintype "passive"))
      (node (ref "D36") (pin "5") (pinfunction "DP_5") (pintype "passive"))
      (node (ref "D37") (pin "5") (pinfunction "DP_5") (pintype "passive"))
      (node (ref "D38") (pin "5") (pinfunction "DP_5") (pintype "passive"))
      (node (ref "D39") (pin "5") (pinfunction "DP_5") (pintype "passive"))
      (node (ref "D40") (pin "5") (pinfunction "DP_5") (pintype "passive"))
      (node (ref "D41") (pin "5") (pinfunction "DP_5") (pintype "passive"))
      (node (ref "R62") (pin "2") (pinfunction "2_2") (pintype "passive"))
    )
    (net (code "26") (name "E") (class "Default")
      (node (ref "D34") (pin "1") (pinfunction "E_1") (pintype "passive"))
      (node (ref "D35") (pin "1") (pinfunction "E_1") (pintype "passive"))
      (node (ref "D36") (pin "1") (pinfunction "E_1") (pintype "passive"))
      (node (ref "D37") (pin "1") (pinfunction "E_1") (pintype "passive"))
      (node (ref "D38") (pin "1") (pinfunction "E_1") (pintype "passive"))
      (node (ref "D39") (pin "1") (pinfunction "E_1") (pintype "passive"))
      (node (ref "D40") (pin "1") (pinfunction "E_1") (pintype "passive"))
      (node (ref "D41") (pin "1") (pinfunction "E_1") (pintype "passive"))
      (node (ref "R59") (pin "2") (pinfunction "2_2") (pintype "passive"))
    )
    (net (code "27") (name "F") (class "Default")
      (node (ref "D34") (pin "9") (pinfunction "F_9") (pintype "passive"))
      (node (ref "D35") (pin "9") (pinfunction "F_9") (pintype "passive"))
      (node (ref "D36") (pin "9") (pinfunction "F_9") (pintype "passive"))
      (node (ref "D37") (pin "9") (pinfunction "F_9") (pintype "passive"))
      (node (ref "D38") (pin "9") (pinfunction "F_9") (pintype "passive"))
      (node (ref "D39") (pin "9") (pinfunction "F_9") (pintype "passive"))
      (node (ref "D40") (pin "9") (pinfunction "F_9") (pintype "passive"))
      (node (ref "D41") (pin "9") (pinfunction "F_9") (pintype "passive"))
      (node (ref "R60") (pin "2") (pinfunction "2_2") (pintype "passive"))
    )
    (net (code "28") (name "G") (class "Default")
      (node (ref "D34") (pin "10") (pinfunction "G_10") (pintype "passive"))
      (node (ref "D35") (pin "10") (pinfunction "G_10") (pintype "passive"))
      (node (ref "D36") (pin "10") (pinfunction "G_10") (pintype "passive"))
      (node (ref "D37") (pin "10") (pinfunction "G_10") (pintype "passive"))
      (node (ref "D38") (pin "10") (pinfunction "G_10") (pintype "passive"))
      (node (ref "D39") (pin "10") (pinfunction "G_10") (pintype "passive"))
      (node (ref "D40") (pin "10") (pinfunction "G_10") (pintype "passive"))
      (node (ref "D41") (pin "10") (pinfunction "G_10") (pintype "passive"))
      (node (ref "R61") (pin "2") (pinfunction "2_2") (pintype "passive"))
    )
    (net (code "29") (name "GND") (class "Default")
      (node (ref "C20") (pin "1") (pinfunction "1_1") (pintype "passive"))
      (node (ref "C21") (pin "1") (pinfunction "1_1") (pintype "passive"))
      (node (ref "C22") (pin "1") (pinfunction "1_1") (pintype "passive"))
      (node (ref "C23") (pin "1") (pinfunction "1_1") (pintype "passive"))
      (node (ref "C24") (pin "1") (pinfunction "1_1") (pintype "passive"))
      (node (ref "C25") (pin "1") (pinfunction "1_1") (pintype "passive"))
      (node (ref "C26") (pin "2") (pinfunction "2_2") (pintype "passive"))
      (node (ref "C27") (pin "1") (pinfunction "1_1") (pintype "passive"))
      (node (ref "C28") (pin "2") (pinfunction "2_2") (pintype "passive"))
      (node (ref "C29") (pin "2") (pinfunction "2_2") (pintype "passive"))
      (node (ref "C31") (pin "1") (pinfunction "1_1") (pintype "passive"))
      (node (ref "P13") (pin "1") (pinfunction "1_1") (pintype "passive"))
      (node (ref "P13") (pin "16") (pinfunction "16_16") (pintype "passive"))
      (node (ref "P13") (pin "5") (pinfunction "5_5") (pintype "passive"))
      (node (ref "P14") (pin "1") (pinfunction "1_1") (pintype "passive"))
      (node (ref "P14") (pin "20") (pinfunction "20_20") (pintype "passive"))
      (node (ref "P14") (pin "5") (pinfunction "5_5") (pintype "passive"))
      (node (ref "P31") (pin "6") (pinfunction "6_6") (pintype "passive"))
      (node (ref "Q2") (pin "3") (pinfunction "E_3") (pintype "passive"))
      (node (ref "Q3") (pin "3") (pinfunction "E_3") (pintype "passive"))
      (node (ref "Q4") (pin "3") (pinfunction "E_3") (pintype "passive"))
      (node (ref "Q5") (pin "3") (pinfunction "E_3") (pintype "passive"))
      (node (ref "Q6") (pin "3") (pinfunction "E_3") (pintype "passive"))
      (node (ref "Q7") (pin "3") (pinfunction "E_3") (pintype "passive"))
      (node (ref "Q8") (pin "3") (pinfunction "E_3") (pintype "passive"))
      (node (ref "Q9") (pin "3") (pinfunction "E_3") (pintype "passive"))
      (node (ref "R41") (pin "1") (pinfunction "TOP_1") (pintype "passive"))
      (node (ref "SS2") (pin "3") (pinfunction "3_3") (pintype "passive"))
      (node (ref "SS3") (pin "3") (pinfunction "3_3") (pintype "passive"))
      (node (ref "SS4") (pin "3") (pinfunction "3_3") (pintype "passive"))
      (node (ref "SS5") (pin "3") (pinfunction "3_3") (pintype "passive"))
      (node (ref "U14") (pin "5") (pinfunction "VSS_5") (pintype "power_in"))
      (node (ref "U15") (pin "4") (pinfunction "VSS_4") (pintype "power_in"))
      (node (ref "U16") (pin "5") (pinfunction "AGND_5") (pintype "power_in"))
      (node (ref "U17") (pin "4") (pinfunction "GND_4") (pintype "power_in"))
      (node (ref "U18") (pin "12") (pinfunction "GND_12") (pintype "power_in"))
      (node (ref "U18") (pin "13") (pinfunction "GND_13") (pintype "power_in"))
      (node (ref "U18") (pin "4") (pinfunction "GND_4") (pintype "power_in"))
      (node (ref "U18") (pin "5") (pinfunction "GND_5") (pintype "power_in"))
    )
    (net (code "30") (name "Net-(P17-Pad1)") (class "Default")
      (node (ref "P17") (pin "1") (pinfunction "1_1") (pintype "passive"))
      (node (ref "R33") (pin "1") (pinfunction "1_1") (pintype "passive"))
      (node (ref "S12") (pin "1") (pinfunction "1_1") (pintype "passive"))
      (node (ref "S12") (pin "2") (pinfunction "2_2") (pintype "passive"))
      (node (ref "S16") (pin "1") (pinfunction "1_1") (pintype "passive"))
      (node (ref "S16") (pin "2") (pinfunction "2_2") (pintype "passive"))
      (node (ref "S20") (pin "1") (pinfunction "1_1") (pintype "passive"))
      (node (ref "S20") (pin "2") (pinfunction "2_2") (pintype "passive"))
      (node (ref "S24") (pin "1") (pinfunction "1_1") (pintype "passive"))
      (node (ref "S24") (pin "2") (pinfunction "2_2") (pintype "passive"))
    )
    (net (code "31") (name "Net-(P17-Pad2)") (class "Default")
      (node (ref "P17") (pin "2") (pinfunction "2_2") (pintype "passive"))
      (node (ref "R66") (pin "1") (pinfunction "1_1") (pintype "passive"))
      (node (ref "S13") (pin "1") (pinfunction "1_1") (pintype "passive"))
      (node (ref "S13") (pin "2") (pinfunction "2_2") (pintype "passive"))
      (node (ref "S17") (pin "1") (pinfunction "1_1") (pintype "passive"))
      (node (ref "S17") (pin "2") (pinfunction "2_2") (pintype "passive"))
      (node (ref "S21") (pin "1") (pinfunction "1_1") (pintype "passive"))
      (node (ref "S21") (pin "2") (pinfunction "2_2") (pintype "passive"))
      (node (ref "S25") (pin "1") (pinfunction "1_1") (pintype "passive"))
      (node (ref "S25") (pin "2") (pinfunction "2_2") (pintype "passive"))
    )
    (net (code "32") (name "Net-(P17-Pad3)") (class "Default")
      (node (ref "P17") (pin "3") (pinfunction "3_3") (pintype "passive"))
      (node (ref "R67") (pin "1") (pinfunction "1_1") (pintype "passive"))
      (node (ref "S14") (pin "1") (pinfunction "1_1") (pintype "passive"))
      (node (ref "S14") (pin "2") (pinfunction "2_2") (pintype "passive"))
      (node (ref "S18") (pin "1") (pinfunction "1_1") (pintype "passive"))
      (node (ref "S18") (pin "2") (pinfunction "2_2") (pintype "passive"))
      (node (ref "S22") (pin "1") (pinfunction "1_1") (pintype "passive"))
      (node (ref "S22") (pin "2") (pinfunction "2_2") (pintype "passive"))
      (node (ref "S26") (pin "1") (pinfunction "1_1") (pintype "passive"))
      (node (ref "S26") (pin "2") (pinfunction "2_2") (pintype "passive"))
    )
    (net (code "33") (name "Net-(P17-Pad4)") (class "Default")
      (node (ref "P17") (pin "4") (pinfunction "4_4") (pintype "passive"))
      (node (ref "R68") (pin "1") (pinfunction "1_1") (pintype "passive"))
      (node (ref "S15") (pin "1") (pinfunction "1_1") (pintype "passive"))
      (node (ref "S15") (pin "2") (pinfunction "2_2") (pintype "passive"))
      (node (ref "S19") (pin "1") (pinfunction "1_1") (pintype "passive"))
      (node (ref "S19") (pin "2") (pinfunction "2_2") (pintype "passive"))
      (node (ref "S23") (pin "1") (pinfunction "1_1") (pintype "passive"))
      (node (ref "S23") (pin "2") (pinfunction "2_2") (pintype "passive"))
      (node (ref "S27") (pin "1") (pinfunction "1_1") (pintype "passive"))
      (node (ref "S27") (pin "2") (pinfunction "2_2") (pintype "passive"))
    )
    (net (code "34") (name "Net-(P18-Pad1)") (class "Default")
      (node (ref "P18") (pin "1") (pinfunction "1_1") (pintype "passive"))
      (node (ref "S12") (pin "3") (pinfunction "3_3") (pintype "passive"))
      (node (ref "S12") (pin "4") (pinfunction "4_4") (pintype "passive"))
      (node (ref "S13") (pin "3") (pinfunction "3_3") (pintype "passive"))
      (node (ref "S13") (pin "4") (pinfunction "4_4") (pintype "passive"))
      (node (ref "S14") (pin "3") (pinfunction "3_3") (pintype "passive"))
      (node (ref "S14") (pin "4") (pinfunction "4_4") (pintype "passive"))
      (node (ref "S15") (pin "3") (pinfunction "3_3") (pintype "passive"))
      (node (ref "S15") (pin "4") (pinfunction "4_4") (pintype "passive"))
    )
    (net (code "35") (name "Net-(P18-Pad2)") (class "Default")
      (node (ref "P18") (pin "2") (pinfunction "2_2") (pintype "passive"))
      (node (ref "S16") (pin "3") (pinfunction "3_3") (pintype "passive"))
      (node (ref "S16") (pin "4") (pinfunction "4_4") (pintype "passive"))
      (node (ref "S17") (pin "3") (pinfunction "3_3") (pintype "passive"))
      (node (ref "S17") (pin "4") (pinfunction "4_4") (pintype "passive"))
      (node (ref "S18") (pin "3") (pinfunction "3_3") (pintype "passive"))
      (node (ref "S18") (pin "4") (pinfunction "4_4") (pintype "passive"))
      (node (ref "S19") (pin "3") (pinfunction "3_3") (pintype "passive"))
      (node (ref "S19") (pin "4") (pinfunction "4_4") (pintype "passive"))
    )
    (net (code "36") (name "Net-(P18-Pad3)") (class "Default")
      (node (ref "P18") (pin "3") (pinfunction "3_3") (pintype "passive"))
      (node (ref "S20") (pin "3") (pinfunction "3_3") (pintype "passive"))
      (node (ref "S20") (pin "4") (pinfunction "4_4") (pintype "passive"))
      (node (ref "S21") (pin "3") (pinfunction "3_3") (pintype "passive"))
      (node (ref "S21") (pin "4") (pinfunction "4_4") (pintype "passive"))
      (node (ref "S22") (pin "3") (pinfunction "3_3") (pintype "passive"))
      (node (ref "S22") (pin "4") (pinfunction "4_4") (pintype "passive"))
      (node (ref "S23") (pin "3") (pinfunction "3_3") (pintype "passive"))
      (node (ref "S23") (pin "4") (pinfunction "4_4") (pintype "passive"))
    )
    (net (code "37") (name "Net-(P18-Pad4)") (class "Default")
      (node (ref "P18") (pin "4") (pinfunction "4_4") (pintype "passive"))
      (node (ref "S24") (pin "3") (pinfunction "3_3") (pintype "passive"))
      (node (ref "S24") (pin "4") (pinfunction "4_4") (pintype "passive"))
      (node (ref "S25") (pin "3") (pinfunction "3_3") (pintype "passive"))
      (node (ref "S25") (pin "4") (pinfunction "4_4") (pintype "passive"))
      (node (ref "S26") (pin "3") (pinfunction "3_3") (pintype "passive"))
      (node (ref "S26") (pin "4") (pinfunction "4_4") (pintype "passive"))
      (node (ref "S27") (pin "3") (pinfunction "3_3") (pintype "passive"))
      (node (ref "S27") (pin "4") (pinfunction "4_4") (pintype "passive"))
    )
    (net (code "38") (name "Net-(P32-Pad1)") (class "Default")
      (node (ref "P32") (pin "1") (pinfunction "1_1") (pintype "passive"))
      (node (ref "R73") (pin "2") (pinfunction "2_2") (pintype "passive"))
    )
    (net (code "39") (name "Net-(P32-Pad2)") (class "Default")
      (node (ref "P32") (pin "2") (pinfunction "2_2") (pintype "passive"))
      (node (ref "R74") (pin "2") (pinfunction "2_2") (pintype "passive"))
    )
    (net (code "40") (name "Net-(P32-Pad3)") (class "Default")
      (node (ref "P32") (pin "3") (pinfunction "3_3") (pintype "passive"))
      (node (ref "R75") (pin "2") (pinfunction "2_2") (pintype "passive"))
    )
    (net (code "41") (name "Net-(P32-Pad4)") (class "Default")
      (node (ref "P32") (pin "4") (pinfunction "4_4") (pintype "passive"))
      (node (ref "R76") (pin "2") (pinfunction "2_2") (pintype "passive"))
    )
    (net (code "42") (name "Net-(P32-Pad5)") (class "Default")
      (node (ref "P32") (pin "5") (pinfunction "5_5") (pintype "passive"))
      (node (ref "R77") (pin "2") (pinfunction "2_2") (pintype "passive"))
    )
    (net (code "43") (name "Net-(P32-Pad6)") (class "Default")
      (node (ref "P32") (pin "6") (pinfunction "6_6") (pintype "passive"))
      (node (ref "R78") (pin "2") (pinfunction "2_2") (pintype "passive"))
    )
    (net (code "44") (name "Net-(P32-Pad7)") (class "Default")
      (node (ref "P32") (pin "7") (pinfunction "7_7") (pintype "passive"))
      (node (ref "R79") (pin "2") (pinfunction "2_2") (pintype "passive"))
    )
    (net (code "45") (name "Net-(P32-Pad8)") (class "Default")
      (node (ref "P32") (pin "8") (pinfunction "8_8") (pintype "passive"))
      (node (ref "R80") (pin "2") (pinfunction "2_2") (pintype "passive"))
    )
    (net (code "46") (name "Net-(P33-Pad1)") (class "Default")
      (node (ref "P33") (pin "1") (pinfunction "1_1") (pintype "passive"))
      (node (ref "P35") (pin "1") (pinfunction "1_1") (pintype "passive"))
      (node (ref "R43") (pin "2") (pinfunction "2_2") (pintype "passive"))
      (node (ref "R50") (pin "2") (pinfunction "2_2") (pintype "passive"))
    )
    (net (code "47") (name "Net-(P33-Pad2)") (class "Default")
      (node (ref "P33") (pin "2") (pinfunction "2_2") (pintype "passive"))
      (node (ref "P35") (pin "2") (pinfunction "2_2") (pintype "passive"))
      (node (ref "R43") (pin "3") (pinfunction "3_3") (pintype "passive"))
      (node (ref "R51") (pin "2") (pinfunction "2_2") (pintype "passive"))
    )
    (net (code "48") (name "Net-(P33-Pad3)") (class "Default")
      (node (ref "P33") (pin "3") (pinfunction "3_3") (pintype "passive"))
      (node (ref "P35") (pin "3") (pinfunction "3_3") (pintype "passive"))
      (node (ref "R43") (pin "4") (pinfunction "4_4") (pintype "passive"))
      (node (ref "R52") (pin "2") (pinfunction "2_2") (pintype "passive"))
    )
    (net (code "49") (name "Net-(P33-Pad4)") (class "Default")
      (node (ref "P33") (pin "4") (pinfunction "4_4") (pintype "passive"))
      (node (ref "P35") (pin "4") (pinfunction "4_4") (pintype "passive"))
      (node (ref "R43") (pin "5") (pinfunction "5_5") (pintype "passive"))
      (node (ref "R53") (pin "2") (pinfunction "2_2") (pintype "passive"))
    )
    (net (code "50") (name "Net-(P33-Pad5)") (class "Default")
      (node (ref "P33") (pin "5") (pinfunction "5_5") (pintype "passive"))
      (node (ref "P35") (pin "5") (pinfunction "5_5") (pintype "passive"))
      (node (ref "R43") (pin "6") (pinfunction "6_6") (pintype "passive"))
      (node (ref "R54") (pin "2") (pinfunction "2_2") (pintype "passive"))
    )
    (net (code "51") (name "Net-(P33-Pad6)") (class "Default")
      (node (ref "P33") (pin "6") (pinfunction "6_6") (pintype "passive"))
      (node (ref "P35") (pin "6") (pinfunction "6_6") (pintype "passive"))
      (node (ref "R43") (pin "7") (pinfunction "7_7") (pintype "passive"))
      (node (ref "R63") (pin "2") (pinfunction "2_2") (pintype "passive"))
    )
    (net (code "52") (name "Net-(P33-Pad7)") (class "Default")
      (node (ref "P33") (pin "7") (pinfunction "7_7") (pintype "passive"))
      (node (ref "P35") (pin "7") (pinfunction "7_7") (pintype "passive"))
      (node (ref "R43") (pin "8") (pinfunction "8_8") (pintype "passive"))
      (node (ref "R64") (pin "2") (pinfunction "2_2") (pintype "passive"))
    )
    (net (code "53") (name "Net-(P33-Pad8)") (class "Default")
      (node (ref "P33") (pin "8") (pinfunction "8_8") (pintype "passive"))
      (node (ref "P35") (pin "8") (pinfunction "8_8") (pintype "passive"))
      (node (ref "R43") (pin "9") (pinfunction "9_9") (pintype "passive"))
      (node (ref "R65") (pin "2") (pinfunction "2_2") (pintype "passive"))
    )
    (net (code "54") (name "Net-(P43-Pad1)") (class "Default")
      (node (ref "P43") (pin "1") (pinfunction "1_1") (pintype "passive"))
      (node (ref "R62") (pin "1") (pinfunction "1_1") (pintype "passive"))
    )
    (net (code "55") (name "Net-(P43-Pad2)") (class "Default")
      (node (ref "P43") (pin "2") (pinfunction "2_2") (pintype "passive"))
      (node (ref "R61") (pin "1") (pinfunction "1_1") (pintype "passive"))
    )
    (net (code "56") (name "Net-(P43-Pad3)") (class "Default")
      (node (ref "P43") (pin "3") (pinfunction "3_3") (pintype "passive"))
      (node (ref "R60") (pin "1") (pinfunction "1_1") (pintype "passive"))
    )
    (net (code "57") (name "Net-(P43-Pad4)") (class "Default")
      (node (ref "P43") (pin "4") (pinfunction "4_4") (pintype "passive"))
      (node (ref "R59") (pin "1") (pinfunction "1_1") (pintype "passive"))
    )
    (net (code "58") (name "Net-(P43-Pad5)") (class "Default")
      (node (ref "P43") (pin "5") (pinfunction "5_5") (pintype "passive"))
      (node (ref "R58") (pin "1") (pinfunction "1_1") (pintype "passive"))
    )
    (net (code "59") (name "Net-(P43-Pad6)") (class "Default")
      (node (ref "P43") (pin "6") (pinfunction "6_6") (pintype "passive"))
      (node (ref "R57") (pin "1") (pinfunction "1_1") (pintype "passive"))
    )
    (net (code "60") (name "Net-(P43-Pad7)") (class "Default")
      (node (ref "P43") (pin "7") (pinfunction "7_7") (pintype "passive"))
      (node (ref "R56") (pin "1") (pinfunction "1_1") (pintype "passive"))
    )
    (net (code "61") (name "Net-(P43-Pad8)") (class "Default")
      (node (ref "P43") (pin "8") (pinfunction "8_8") (pintype "passive"))
      (node (ref "R55") (pin "1") (pinfunction "1_1") (pintype "passive"))
    )
    (net (code "62") (name "Net-(R33-Pad2)") (class "Default")
      (node (ref "R33") (pin "2") (pinfunction "2_2") (pintype "passive"))
      (node (ref "R66") (pin "2") (pinfunction "2_2") (pintype "passive"))
      (node (ref "R67") (pin "2") (pinfunction "2_2") (pintype "passive"))
      (node (ref "R68") (pin "2") (pinfunction "2_2") (pintype "passive"))
      (node (ref "SS4") (pin "2") (pinfunction "2_2") (pintype "passive"))
    )
    (net (code "63") (name "Net-(R41-TAP)") (class "Default")
      (node (ref "P13") (pin "3") (pinfunction "3_3") (pintype "passive"))
      (node (ref "R41") (pin "3") (pinfunction "TAP_3") (pintype "passive"))
    )
    (net (code "64") (name "Net-(R43-Pad1)") (class "Default")
      (node (ref "R43") (pin "1") (pinfunction "1_1") (pintype "passive"))
      (node (ref "SS3") (pin "2") (pinfunction "2_2") (pintype "passive"))
    )
    (net (code "65") (name "Net-(R50-Pad1)") (class "Default")
      (node (ref "R50") (pin "1") (pinfunction "1_1") (pintype "passive"))
      (node (ref "S2") (pin "3") (pinfunction "3_3") (pintype "passive"))
      (node (ref "S2") (pin "4") (pinfunction "4_4") (pintype "passive"))
    )
    (net (code "66") (name "Net-(R51-Pad1)") (class "Default")
      (node (ref "R51") (pin "1") (pinfunction "1_1") (pintype "passive"))
      (node (ref "S3") (pin "3") (pinfunction "3_3") (pintype "passive"))
      (node (ref "S3") (pin "4") (pinfunction "4_4") (pintype "passive"))
    )
    (net (code "67") (name "Net-(R52-Pad1)") (class "Default")
      (node (ref "R52") (pin "1") (pinfunction "1_1") (pintype "passive"))
      (node (ref "S4") (pin "3") (pinfunction "3_3") (pintype "passive"))
      (node (ref "S4") (pin "4") (pinfunction "4_4") (pintype "passive"))
    )
    (net (code "68") (name "Net-(R53-Pad1)") (class "Default")
      (node (ref "R53") (pin "1") (pinfunction "1_1") (pintype "passive"))
      (node (ref "S5") (pin "3") (pinfunction "3_3") (pintype "passive"))
      (node (ref "S5") (pin "4") (pinfunction "4_4") (pintype "passive"))
    )
    (net (code "69") (name "Net-(R54-Pad1)") (class "Default")
      (node (ref "R54") (pin "1") (pinfunction "1_1") (pintype "passive"))
      (node (ref "S6") (pin "3") (pinfunction "3_3") (pintype "passive"))
      (node (ref "S6") (pin "4") (pinfunction "4_4") (pintype "passive"))
    )
    (net (code "70") (name "Net-(R63-Pad1)") (class "Default")
      (node (ref "R63") (pin "1") (pinfunction "1_1") (pintype "passive"))
      (node (ref "S7") (pin "3") (pinfunction "3_3") (pintype "passive"))
      (node (ref "S7") (pin "4") (pinfunction "4_4") (pintype "passive"))
    )
    (net (code "71") (name "Net-(R64-Pad1)") (class "Default")
      (node (ref "R64") (pin "1") (pinfunction "1_1") (pintype "passive"))
      (node (ref "S8") (pin "3") (pinfunction "3_3") (pintype "passive"))
      (node (ref "S8") (pin "4") (pinfunction "4_4") (pintype "passive"))
    )
    (net (code "72") (name "Net-(R65-Pad1)") (class "Default")
      (node (ref "R65") (pin "1") (pinfunction "1_1") (pintype "passive"))
      (node (ref "S9") (pin "3") (pinfunction "3_3") (pintype "passive"))
      (node (ref "S9") (pin "4") (pinfunction "4_4") (pintype "passive"))
    )
    (net (code "73") (name "Net-(S2-Pad1)") (class "Default")
      (node (ref "S2") (pin "1") (pinfunction "1_1") (pintype "passive"))
      (node (ref "S2") (pin "2") (pinfunction "2_2") (pintype "passive"))
      (node (ref "S3") (pin "1") (pinfunction "1_1") (pintype "passive"))
      (node (ref "S3") (pin "2") (pinfunction "2_2") (pintype "passive"))
      (node (ref "S4") (pin "1") (pinfunction "1_1") (pintype "passive"))
      (node (ref "S4") (pin "2") (pinfunction "2_2") (pintype "passive"))
      (node (ref "S5") (pin "1") (pinfunction "1_1") (pintype "passive"))
      (node (ref "S5") (pin "2") (pinfunction "2_2") (pintype "passive"))
      (node (ref "S6") (pin "1") (pinfunction "1_1") (pintype "passive"))
      (node (ref "S6") (pin "2") (pinfunction "2_2") (pintype "passive"))
      (node (ref "S7") (pin "1") (pinfunction "1_1") (pintype "passive"))
      (node (ref "S7") (pin "2") (pinfunction "2_2") (pintype "passive"))
      (node (ref "S8") (pin "1") (pinfunction "1_1") (pintype "passive"))
      (node (ref "S8") (pin "2") (pinfunction "2_2") (pintype "passive"))
      (node (ref "S9") (pin "1") (pinfunction "1_1") (pintype "passive"))
      (node (ref "S9") (pin "2") (pinfunction "2_2") (pintype "passive"))
      (node (ref "SS2") (pin "2") (pinfunction "2_2") (pintype "passive"))
    )
    (net (code "74") (name "Net-(U14-CLK)") (class "Default")
      (node (ref "P28") (pin "2") (pinfunction "2_2") (pintype "passive"))
      (node (ref "P30") (pin "2") (pinfunction "2_2") (pintype "passive"))
      (node (ref "U14") (pin "2") (pinfunction "CLK_2") (pintype "input"))
    )
    (net (code "75") (name "Net-(U14-CS)") (class "Default")
      (node (ref "P28") (pin "1") (pinfunction "1_1") (pintype "passive"))
      (node (ref "P30") (pin "1") (pinfunction "1_1") (pintype "passive"))
      (node (ref "U14") (pin "1") (pinfunction "CS_1") (pintype "input"))
    )
    (net (code "76") (name "Net-(U14-DI)") (class "Default")
      (node (ref "P28") (pin "3") (pinfunction "3_3") (pintype "passive"))
      (node (ref "P30") (pin "3") (pinfunction "3_3") (pintype "passive"))
      (node (ref "U14") (pin "3") (pinfunction "DI_3") (pintype "input"))
    )
    (net (code "77") (name "Net-(U14-DO)") (class "Default")
      (node (ref "P28") (pin "4") (pinfunction "4_4") (pintype "passive"))
      (node (ref "P30") (pin "4") (pinfunction "4_4") (pintype "passive"))
      (node (ref "U14") (pin "4") (pinfunction "DO_4") (pintype "output"))
    )
    (net (code "78") (name "Net-(U14-ORG)") (class "Default")
      (node (ref "SS5") (pin "2") (pinfunction "2_2") (pintype "passive"))
      (node (ref "U14") (pin "6") (pinfunction "ORG_6") (pintype "bidirectional"))
    )
    (net (code "79") (name "Net-(U15-SCL)") (class "Default")
      (node (ref "P34") (pin "1") (pinfunction "1_1") (pintype "passive"))
      (node (ref "P36") (pin "1") (pinfunction "1_1") (pintype "passive"))
      (node (ref "U15") (pin "6") (pinfunction "SCL_6") (pintype "input"))
    )
    (net (code "80") (name "Net-(U15-SDA)") (class "Default")
      (node (ref "P34") (pin "2") (pinfunction "2_2") (pintype "passive"))
      (node (ref "P36") (pin "2") (pinfunction "2_2") (pintype "passive"))
      (node (ref "U15") (pin "5") (pinfunction "SDA_5") (pintype "bidirectional"))
    )
    (net (code "81") (name "Net-(U16-DIN)") (class "Default")
      (node (ref "P37") (pin "1") (pinfunction "1_1") (pintype "passive"))
      (node (ref "P41") (pin "1") (pinfunction "1_1") (pintype "passive"))
      (node (ref "U16") (pin "1") (pinfunction "DIN_1") (pintype "input"))
    )
    (net (code "82") (name "Net-(U16-OUT)") (class "Default")
      (node (ref "P39") (pin "1") (pinfunction "1_1") (pintype "passive"))
      (node (ref "P39") (pin "2") (pinfunction "2_2") (pintype "passive"))
      (node (ref "U16") (pin "7") (pinfunction "OUT_7") (pintype "output"))
    )
    (net (code "83") (name "Net-(U16-SCLK)") (class "Default")
      (node (ref "P37") (pin "2") (pinfunction "2_2") (pintype "passive"))
      (node (ref "P41") (pin "2") (pinfunction "2_2") (pintype "passive"))
      (node (ref "U16") (pin "2") (pinfunction "SCLK_2") (pintype "input"))
    )
    (net (code "84") (name "Net-(U16-~{CS})") (class "Default")
      (node (ref "P37") (pin "3") (pinfunction "3_3") (pintype "passive"))
      (node (ref "P41") (pin "3") (pinfunction "3_3") (pintype "passive"))
      (node (ref "U16") (pin "3") (pinfunction "~{CS}_3") (pintype "input"))
    )
    (net (code "85") (name "Net-(U17-CE)") (class "Default")
      (node (ref "P44") (pin "1") (pinfunction "1_1") (pintype "passive"))
      (node (ref "P45") (pin "1") (pinfunction "1_1") (pintype "passive"))
      (node (ref "U17") (pin "5") (pinfunction "CE_5") (pintype "input"))
    )
    (net (code "86") (name "Net-(U17-I{slash}O)") (class "Default")
      (node (ref "P44") (pin "2") (pinfunction "2_2") (pintype "passive"))
      (node (ref "P45") (pin "2") (pinfunction "2_2") (pintype "passive"))
      (node (ref "U17") (pin "6") (pinfunction "I/O_6") (pintype "bidirectional"))
    )
    (net (code "87") (name "Net-(U17-SCLK)") (class "Default")
      (node (ref "P44") (pin "3") (pinfunction "3_3") (pintype "passive"))
      (node (ref "P45") (pin "3") (pinfunction "3_3") (pintype "passive"))
      (node (ref "U17") (pin "7") (pinfunction "SCLK_7") (pintype "input"))
    )
    (net (code "88") (name "Net-(U17-X1)") (class "Default")
      (node (ref "C28") (pin "1") (pinfunction "1_1") (pintype "passive"))
      (node (ref "U17") (pin "2") (pinfunction "X1_2") (pintype "bidirectional"))
      (node (ref "Y2") (pin "1") (pinfunction "OSC1_1") (pintype "passive"))
    )
    (net (code "89") (name "Net-(U17-X2)") (class "Default")
      (node (ref "C29") (pin "1") (pinfunction "1_1") (pintype "passive"))
      (node (ref "U17") (pin "3") (pinfunction "X2_3") (pintype "bidirectional"))
      (node (ref "Y2") (pin "2") (pinfunction "OSC2_2") (pintype "passive"))
    )
    (net (code "90") (name "Net-(U18-ENABLE1)") (class "Default")
      (node (ref "S10") (pin "3") (pinfunction "3_3") (pintype "passive"))
      (node (ref "S10") (pin "4") (pinfunction "4_4") (pintype "passive"))
      (node (ref "U18") (pin "1") (pinfunction "ENABLE1_1") (pintype "input"))
    )
    (net (code "91") (name "Net-(U18-ENABLE2)") (class "Default")
      (node (ref "S11") (pin "3") (pinfunction "3_3") (pintype "passive"))
      (node (ref "S11") (pin "4") (pinfunction "4_4") (pintype "passive"))
      (node (ref "U18") (pin "9") (pinfunction "ENABLE2_9") (pintype "input"))
    )
    (net (code "92") (name "Net-(U18-INPUT1)") (class "Default")
      (node (ref "P47") (pin "4") (pinfunction "4_4") (pintype "passive"))
      (node (ref "P49") (pin "4") (pinfunction "4_4") (pintype "passive"))
      (node (ref "U18") (pin "2") (pinfunction "INPUT1_2") (pintype "input"))
    )
    (net (code "93") (name "Net-(U18-INPUT2)") (class "Default")
      (node (ref "P47") (pin "3") (pinfunction "3_3") (pintype "passive"))
      (node (ref "P49") (pin "3") (pinfunction "3_3") (pintype "passive"))
      (node (ref "U18") (pin "7") (pinfunction "INPUT2_7") (pintype "input"))
    )
    (net (code "94") (name "Net-(U18-INPUT3)") (class "Default")
      (node (ref "P47") (pin "2") (pinfunction "2_2") (pintype "passive"))
      (node (ref "P49") (pin "2") (pinfunction "2_2") (pintype "passive"))
      (node (ref "U18") (pin "10") (pinfunction "INPUT3_10") (pintype "input"))
    )
    (net (code "95") (name "Net-(U18-INPUT4)") (class "Default")
      (node (ref "P47") (pin "1") (pinfunction "1_1") (pintype "passive"))
      (node (ref "P49") (pin "1") (pinfunction "1_1") (pintype "passive"))
      (node (ref "U18") (pin "15") (pinfunction "INPUT4_15") (pintype "input"))
    )
    (net (code "96") (name "Net-(U18-OUTPUT1)") (class "Default")
      (node (ref "P48") (pin "1") (pinfunction "1_1") (pintype "passive"))
      (node (ref "U18") (pin "3") (pinfunction "OUTPUT1_3") (pintype "output"))
    )
    (net (code "97") (name "Net-(U18-OUTPUT2)") (class "Default")
      (node (ref "P48") (pin "2") (pinfunction "2_2") (pintype "passive"))
      (node (ref "U18") (pin "6") (pinfunction "OUTPUT2_6") (pintype "output"))
    )
    (net (code "98") (name "Net-(U18-OUTPUT3)") (class "Default")
      (node (ref "P48") (pin "3") (pinfunction "3_3") (pintype "passive"))
      (node (ref "U18") (pin "11") (pinfunction "OUTPUT3_11") (pintype "output"))
    )
    (net (code "99") (name "Net-(U18-OUTPUT4)") (class "Default")
      (node (ref "P48") (pin "4") (pinfunction "4_4") (pintype "passive"))
      (node (ref "U18") (pin "14") (pinfunction "OUTPUT4_14") (pintype "output"))
    )
    (net (code "100") (name "VCC") (class "Default")
      (node (ref "C20") (pin "2") (pinfunction "2_2") (pintype "passive"))
      (node (ref "C21") (pin "2") (pinfunction "2_2") (pintype "passive"))
      (node (ref "C22") (pin "2") (pinfunction "2_2") (pintype "passive"))
      (node (ref "C23") (pin "2") (pinfunction "2_2") (pintype "passive"))
      (node (ref "C24") (pin "2") (pinfunction "2_2") (pintype "passive"))
      (node (ref "C25") (pin "2") (pinfunction "2_2") (pintype "passive"))
      (node (ref "C26") (pin "1") (pinfunction "1_1") (pintype "passive"))
      (node (ref "C27") (pin "2") (pinfunction "2_2") (pintype "passive"))
      (node (ref "P13") (pin "15") (pinfunction "15_15") (pintype "passive"))
      (node (ref "P13") (pin "2") (pinfunction "2_2") (pintype "passive"))
      (node (ref "P14") (pin "19") (pinfunction "19_19") (pintype "passive"))
      (node (ref "P14") (pin "2") (pinfunction "2_2") (pintype "passive"))
      (node (ref "P31") (pin "1") (pinfunction "1_1") (pintype "passive"))
      (node (ref "R41") (pin "2") (pinfunction "BOT_2") (pintype "passive"))
      (node (ref "R42") (pin "2") (pinfunction "BOT_2") (pintype "passive"))
      (node (ref "R44") (pin "2") (pinfunction "2_2") (pintype "passive"))
      (node (ref "R45") (pin "2") (pinfunction "2_2") (pintype "passive"))
      (node (ref "R46") (pin "2") (pinfunction "2_2") (pintype "passive"))
      (node (ref "R47") (pin "2") (pinfunction "2_2") (pintype "passive"))
      (node (ref "R48") (pin "2") (pinfunction "2_2") (pintype "passive"))
      (node (ref "R49") (pin "2") (pinfunction "2_2") (pintype "passive"))
      (node (ref "R71") (pin "2") (pinfunction "2_2") (pintype "passive"))
      (node (ref "R72") (pin "2") (pinfunction "2_2") (pintype "passive"))
      (node (ref "S10") (pin "1") (pinfunction "1_1") (pintype "passive"))
      (node (ref "S10") (pin "2") (pinfunction "2_2") (pintype "passive"))
      (node (ref "S11") (pin "1") (pinfunction "1_1") (pintype "passive"))
      (node (ref "S11") (pin "2") (pinfunction "2_2") (pintype "passive"))
      (node (ref "SS2") (pin "1") (pinfunction "1_1") (pintype "passive"))
      (node (ref "SS3") (pin "1") (pinfunction "1_1") (pintype "passive"))
      (node (ref "SS4") (pin "1") (pinfunction "1_1") (pintype "passive"))
      (node (ref "SS5") (pin "1") (pinfunction "1_1") (pintype "passive"))
      (node (ref "U14") (pin "8") (pinfunction "VCC_8") (pintype "power_in"))
      (node (ref "U15") (pin "8") (pinfunction "VCC_8") (pintype "power_in"))
      (node (ref "U16") (pin "6") (pinfunction "REFIN_6") (pintype "input"))
      (node (ref "U16") (pin "8") (pinfunction "VDD_8") (pintype "power_in"))
      (node (ref "U17") (pin "1") (pinfunction "VCC_1") (pintype "power_in"))
      (node (ref "U18") (pin "8") (pinfunction "VS_8") (pintype "power_in"))
    )
    (net (code "101") (name "WP") (class "Default")
      (node (ref "P31") (pin "5") (pinfunction "5_5") (pintype "passive"))
      (node (ref "U15") (pin "7") (pinfunction "WP_7") (pintype "input"))
    )
    (net (code "102") (name "a1") (class "Default")
      (node (ref "P13") (pin "7") (pinfunction "7_7") (pintype "passive"))
      (node (ref "P14") (pin "7") (pinfunction "7_7") (pintype "passive"))
      (node (ref "P15") (pin "3") (pinfunction "3_3") (pintype "passive"))
    )
    (net (code "103") (name "a2") (class "Default")
      (node (ref "P13") (pin "8") (pinfunction "8_8") (pintype "passive"))
      (node (ref "P14") (pin "8") (pinfunction "8_8") (pintype "passive"))
      (node (ref "P15") (pin "4") (pinfunction "4_4") (pintype "passive"))
    )
    (net (code "104") (name "a3") (class "Default")
      (node (ref "P13") (pin "9") (pinfunction "9_9") (pintype "passive"))
      (node (ref "P14") (pin "9") (pinfunction "9_9") (pintype "passive"))
      (node (ref "P15") (pin "5") (pinfunction "5_5") (pintype "passive"))
    )
    (net (code "105") (name "a4") (class "Default")
      (node (ref "P13") (pin "10") (pinfunction "10_10") (pintype "passive"))
      (node (ref "P14") (pin "10") (pinfunction "10_10") (pintype "passive"))
      (node (ref "P15") (pin "6") (pinfunction "6_6") (pintype "passive"))
    )
    (net (code "106") (name "a5") (class "Default")
      (node (ref "P13") (pin "11") (pinfunction "11_11") (pintype "passive"))
      (node (ref "P14") (pin "11") (pinfunction "11_11") (pintype "passive"))
      (node (ref "P15") (pin "7") (pinfunction "7_7") (pintype "passive"))
    )
    (net (code "107") (name "a6") (class "Default")
      (node (ref "P13") (pin "12") (pinfunction "12_12") (pintype "passive"))
      (node (ref "P14") (pin "12") (pinfunction "12_12") (pintype "passive"))
      (node (ref "P15") (pin "8") (pinfunction "8_8") (pintype "passive"))
    )
    (net (code "108") (name "a7") (class "Default")
      (node (ref "P13") (pin "13") (pinfunction "13_13") (pintype "passive"))
      (node (ref "P14") (pin "13") (pinfunction "13_13") (pintype "passive"))
      (node (ref "P15") (pin "9") (pinfunction "9_9") (pintype "passive"))
    )
    (net (code "109") (name "a8") (class "Default")
      (node (ref "P13") (pin "14") (pinfunction "14_14") (pintype "passive"))
      (node (ref "P14") (pin "14") (pinfunction "14_14") (pintype "passive"))
      (node (ref "P15") (pin "10") (pinfunction "10_10") (pintype "passive"))
    )
    (net (code "110") (name "c1") (class "Default")
      (node (ref "P14") (pin "15") (pinfunction "15_15") (pintype "passive"))
      (node (ref "P15") (pin "11") (pinfunction "11_11") (pintype "passive"))
    )
    (net (code "111") (name "c2") (class "Default")
      (node (ref "P14") (pin "16") (pinfunction "16_16") (pintype "passive"))
      (node (ref "P15") (pin "12") (pinfunction "12_12") (pintype "passive"))
    )
    (net (code "112") (name "en") (class "Default")
      (node (ref "P13") (pin "6") (pinfunction "6_6") (pintype "passive"))
      (node (ref "P14") (pin "6") (pinfunction "6_6") (pintype "passive"))
      (node (ref "P15") (pin "2") (pinfunction "2_2") (pintype "passive"))
    )
    (net (code "113") (name "rs") (class "Default")
      (node (ref "P13") (pin "4") (pinfunction "4_4") (pintype "passive"))
      (node (ref "P14") (pin "4") (pinfunction "4_4") (pintype "passive"))
      (node (ref "P15") (pin "1") (pinfunction "1_1") (pintype "passive"))
    )
    (net (code "114") (name "rst") (class "Default")
      (node (ref "P14") (pin "17") (pinfunction "17_17") (pintype "passive"))
      (node (ref "P15") (pin "13") (pinfunction "13_13") (pintype "passive"))
    )
    (net (code "115") (name "unconnected-(D34-CC-Pad8)") (class "Default")
      (node (ref "D34") (pin "8") (pinfunction "CC_8") (pintype "passive"))
    )
    (net (code "116") (name "unconnected-(D35-CC-Pad8)") (class "Default")
      (node (ref "D35") (pin "8") (pinfunction "CC_8") (pintype "passive"))
    )
    (net (code "117") (name "unconnected-(D36-CC-Pad8)") (class "Default")
      (node (ref "D36") (pin "8") (pinfunction "CC_8") (pintype "passive"))
    )
    (net (code "118") (name "unconnected-(D37-CC-Pad8)") (class "Default")
      (node (ref "D37") (pin "8") (pinfunction "CC_8") (pintype "passive"))
    )
    (net (code "119") (name "unconnected-(D38-CC-Pad8)") (class "Default")
      (node (ref "D38") (pin "8") (pinfunction "CC_8") (pintype "passive"))
    )
    (net (code "120") (name "unconnected-(D39-CC-Pad8)") (class "Default")
      (node (ref "D39") (pin "8") (pinfunction "CC_8") (pintype "passive"))
    )
    (net (code "121") (name "unconnected-(D40-CC-Pad8)") (class "Default")
      (node (ref "D40") (pin "8") (pinfunction "CC_8") (pintype "passive"))
    )
    (net (code "122") (name "unconnected-(D41-CC-Pad8)") (class "Default")
      (node (ref "D41") (pin "8") (pinfunction "CC_8") (pintype "passive"))
    )
    (net (code "123") (name "unconnected-(U14-NC-Pad7)") (class "Default")
      (node (ref "U14") (pin "7") (pinfunction "NC_7") (pintype "bidirectional"))
    )
    (net (code "124") (name "unconnected-(U16-DOUT-Pad4)") (class "Default")
      (node (ref "U16") (pin "4") (pinfunction "DOUT_4") (pintype "output"))
    )
    (net (code "125") (name "ve") (class "Default")
      (node (ref "P14") (pin "18") (pinfunction "18_18") (pintype "passive"))
      (node (ref "R42") (pin "1") (pinfunction "TOP_1") (pintype "passive"))
    )
    (net (code "126") (name "vo") (class "Default")
      (node (ref "P14") (pin "3") (pinfunction "3_3") (pintype "passive"))
      (node (ref "R42") (pin "3") (pinfunction "TAP_3") (pintype "passive"))
    )
  )
)
